# Traitement_pwm.net
KiCad netlist of a schematic drawn in Altium Designer
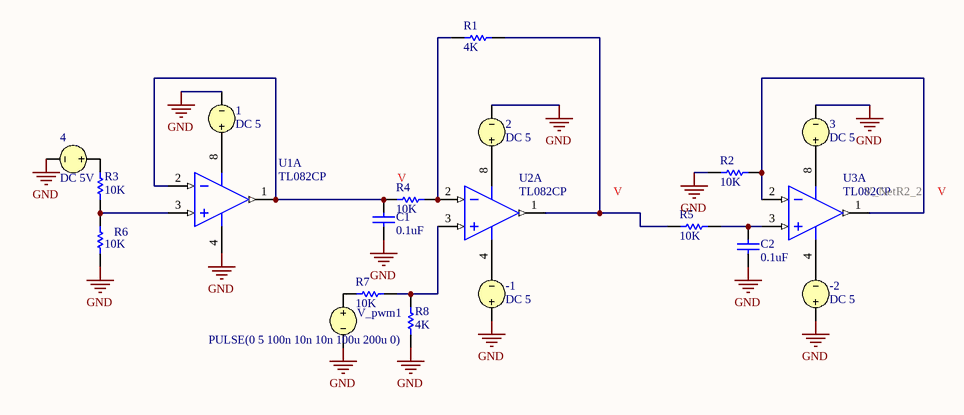
[diagram p0: Traitement_pwm.SchDoc]

(export (version "E")
  (design (tool "Eeschema 10.0.6"))
  (components
    (comp (ref "-1")
      (value "DC 5")
      (description "Voltage Source")
      (fields (field (name "PUBLISHER") "Altium Limited"))
      (libsource (lib "Simulation Generic Components") (part "VSRC"))
    )
    (comp (ref "-2")
      (value "DC 5")
      (description "Voltage Source")
      (fields (field (name "PUBLISHER") "Altium Limited"))
      (libsource (lib "Simulation Generic Components") (part "VSRC"))
    )
    (comp (ref "1")
      (value "DC 5")
      (description "Voltage Source")
      (fields (field (name "PUBLISHER") "Altium Limited"))
      (libsource (lib "Simulation Generic Components") (part "VSRC"))
    )
    (comp (ref "2")
      (value "DC 5")
      (description "Voltage Source")
      (fields (field (name "PUBLISHER") "Altium Limited"))
      (libsource (lib "Simulation Generic Components") (part "VSRC"))
    )
    (comp (ref "3")
      (value "DC 5")
      (description "Voltage Source")
      (fields (field (name "PUBLISHER") "Altium Limited"))
      (libsource (lib "Simulation Generic Components") (part "VSRC"))
    )
    (comp (ref "4")
      (value "DC 5V")
      (description "Voltage Source")
      (fields (field (name "PUBLISHER") "Altium Limited"))
      (libsource (lib "Simulation Generic Components") (part "VSRC"))
    )
    (comp (ref "C1")
      (value "0.1uF")
      (description "Capacitor")
      (libsource (lib "Simulation Generic Components") (part "Capacitor"))
    )
    (comp (ref "C2")
      (value "0.1uF")
      (description "Capacitor")
      (libsource (lib "Simulation Generic Components") (part "Capacitor"))
    )
    (comp (ref "R1")
      (value "4K")
      (description "Resistor")
      (libsource (lib "Simulation Generic Components") (part "Resistor"))
    )
    (comp (ref "R2")
      (value "10K")
      (description "Resistor")
      (libsource (lib "Simulation Generic Components") (part "Resistor"))
    )
    (comp (ref "R3")
      (value "10K")
      (description "Resistor")
      (libsource (lib "Simulation Generic Components") (part "Resistor"))
    )
    (comp (ref "R4")
      (value "10K")
      (description "Resistor")
      (libsource (lib "Simulation Generic Components") (part "Resistor"))
    )
    (comp (ref "R5")
      (value "10K")
      (description "Resistor")
      (libsource (lib "Simulation Generic Components") (part "Resistor"))
    )
    (comp (ref "R6")
      (value "10K")
      (description "Resistor")
      (libsource (lib "Simulation Generic Components") (part "Resistor"))
    )
    (comp (ref "R7")
      (value "10K")
      (description "Resistor")
      (libsource (lib "Simulation Generic Components") (part "Resistor"))
    )
    (comp (ref "R8")
      (value "4K")
      (description "Resistor")
      (libsource (lib "Simulation Generic Components") (part "Resistor"))
    )
    (comp (ref "U1")
      (value "TL082CP")
      (footprint "N08E")
      (description "Wide Bandwidth Dual JFET Input Operational Amplifier, 8-pin MDIP")
      (fields
        (field (name "MANUFACTURER") "National Semiconductor")
        (field (name "PUBLISHER") "Altium Limited")
      )
      (libsource (lib "NSC Amplifier") (part "TL082CP"))
    )
    (comp (ref "U2")
      (value "TL082CP")
      (footprint "N08E")
      (description "Wide Bandwidth Dual JFET Input Operational Amplifier, 8-pin MDIP")
      (fields
        (field (name "MANUFACTURER") "National Semiconductor")
        (field (name "PUBLISHER") "Altium Limited")
      )
      (libsource (lib "NSC Amplifier") (part "TL082CP"))
    )
    (comp (ref "U3")
      (value "TL082CP")
      (footprint "N08E")
      (description "Wide Bandwidth Dual JFET Input Operational Amplifier, 8-pin MDIP")
      (fields
        (field (name "MANUFACTURER") "National Semiconductor")
        (field (name "PUBLISHER") "Altium Limited")
      )
      (libsource (lib "NSC Amplifier") (part "TL082CP"))
    )
    (comp (ref "V_pwm1")
      (value "PULSE(0 5 100n 10n 10n 100u 200u 0)")
      (description "Voltage Source")
      (fields (field (name "PUBLISHER") "Altium Limited"))
      (libsource (lib "Simulation Generic Components") (part "VSRC"))
    )
  )
  (nets
    (net (code "1") (name "GND") (class "Default")
      (node (ref "-1") (pin "1") (pinfunction "1_1") (pintype "passive"))
      (node (ref "-2") (pin "1") (pinfunction "1_1") (pintype "passive"))
      (node (ref "1") (pin "2") (pinfunction "2_2") (pintype "passive"))
      (node (ref "2") (pin "2") (pinfunction "2_2") (pintype "passive"))
      (node (ref "3") (pin "2") (pinfunction "2_2") (pintype "passive"))
      (node (ref "4") (pin "2") (pinfunction "2_2") (pintype "passive"))
      (node (ref "C1") (pin "1") (pinfunction "1_1") (pintype "passive"))
      (node (ref "C2") (pin "1") (pinfunction "1_1") (pintype "passive"))
      (node (ref "R2") (pin "1") (pinfunction "1_1") (pintype "passive"))
      (node (ref "R6") (pin "1") (pinfunction "1_1") (pintype "passive"))
      (node (ref "R8") (pin "2") (pinfunction "2_2") (pintype "passive"))
      (node (ref "U1") (pin "4") (pinfunction "V-_4") (pintype "power_in"))
      (node (ref "V_pwm1") (pin "2") (pinfunction "2_2") (pintype "passive"))
    )
    (net (code "2") (name "Net-(4-Pad1)") (class "Default")
      (node (ref "4") (pin "1") (pinfunction "1_1") (pintype "passive"))
      (node (ref "R3") (pin "1") (pinfunction "1_1") (pintype "passive"))
    )
    (net (code "3") (name "Net-(R7-Pad1)") (class "Default")
      (node (ref "R7") (pin "1") (pinfunction "1_1") (pintype "passive"))
      (node (ref "V_pwm1") (pin "1") (pinfunction "1_1") (pintype "passive"))
    )
    (net (code "4") (name "Net-(U1A-INA+)") (class "Default")
      (node (ref "R3") (pin "2") (pinfunction "2_2") (pintype "passive"))
      (node (ref "R6") (pin "2") (pinfunction "2_2") (pintype "passive"))
      (node (ref "U1") (pin "3") (pinfunction "INA+_3") (pintype "input"))
    )
    (net (code "5") (name "Net-(U1A-INA-)") (class "Default")
      (node (ref "C1") (pin "2") (pinfunction "2_2") (pintype "passive"))
      (node (ref "R4") (pin "1") (pinfunction "1_1") (pintype "passive"))
      (node (ref "U1") (pin "1") (pinfunction "OUTA_1") (pintype "output"))
      (node (ref "U1") (pin "2") (pinfunction "INA-_2") (pintype "input"))
    )
    (net (code "6") (name "Net-(U1A-V+)") (class "Default")
      (node (ref "1") (pin "1") (pinfunction "1_1") (pintype "passive"))
      (node (ref "U1") (pin "8") (pinfunction "V+_8") (pintype "power_in"))
    )
    (net (code "7") (name "Net-(U2A-INA+)") (class "Default")
      (node (ref "R7") (pin "2") (pinfunction "2_2") (pintype "passive"))
      (node (ref "R8") (pin "1") (pinfunction "1_1") (pintype "passive"))
      (node (ref "U2") (pin "3") (pinfunction "INA+_3") (pintype "input"))
    )
    (net (code "8") (name "Net-(U2A-INA-)") (class "Default")
      (node (ref "R1") (pin "1") (pinfunction "1_1") (pintype "passive"))
      (node (ref "R4") (pin "2") (pinfunction "2_2") (pintype "passive"))
      (node (ref "U2") (pin "2") (pinfunction "INA-_2") (pintype "input"))
    )
    (net (code "9") (name "Net-(U2A-OUTA)") (class "Default")
      (node (ref "R1") (pin "2") (pinfunction "2_2") (pintype "passive"))
      (node (ref "R5") (pin "1") (pinfunction "1_1") (pintype "passive"))
      (node (ref "U2") (pin "1") (pinfunction "OUTA_1") (pintype "output"))
    )
    (net (code "10") (name "Net-(U2A-V+)") (class "Default")
      (node (ref "2") (pin "1") (pinfunction "1_1") (pintype "passive"))
      (node (ref "U2") (pin "8") (pinfunction "V+_8") (pintype "power_in"))
    )
    (net (code "11") (name "Net-(U2A-V-)") (class "Default")
      (node (ref "-1") (pin "2") (pinfunction "2_2") (pintype "passive"))
      (node (ref "U2") (pin "4") (pinfunction "V-_4") (pintype "power_in"))
    )
    (net (code "12") (name "Net-(U3A-INA+)") (class "Default")
      (node (ref "C2") (pin "2") (pinfunction "2_2") (pintype "passive"))
      (node (ref "R5") (pin "2") (pinfunction "2_2") (pintype "passive"))
      (node (ref "U3") (pin "3") (pinfunction "INA+_3") (pintype "input"))
    )
    (net (code "13") (name "Net-(U3A-INA-)") (class "Default")
      (node (ref "R2") (pin "2") (pinfunction "2_2") (pintype "passive"))
      (node (ref "U3") (pin "1") (pinfunction "OUTA_1") (pintype "output"))
      (node (ref "U3") (pin "2") (pinfunction "INA-_2") (pintype "input"))
    )
    (net (code "14") (name "Net-(U3A-V+)") (class "Default")
      (node (ref "3") (pin "1") (pinfunction "1_1") (pintype "passive"))
      (node (ref "U3") (pin "8") (pinfunction "V+_8") (pintype "power_in"))
    )
    (net (code "15") (name "Net-(U3A-V-)") (class "Default")
      (node (ref "-2") (pin "2") (pinfunction "2_2") (pintype "passive"))
      (node (ref "U3") (pin "4") (pinfunction "V-_4") (pintype "power_in"))
    )
  )
)
